# e-programmer.net
KiCad netlist of a schematic drawn in EAGLE
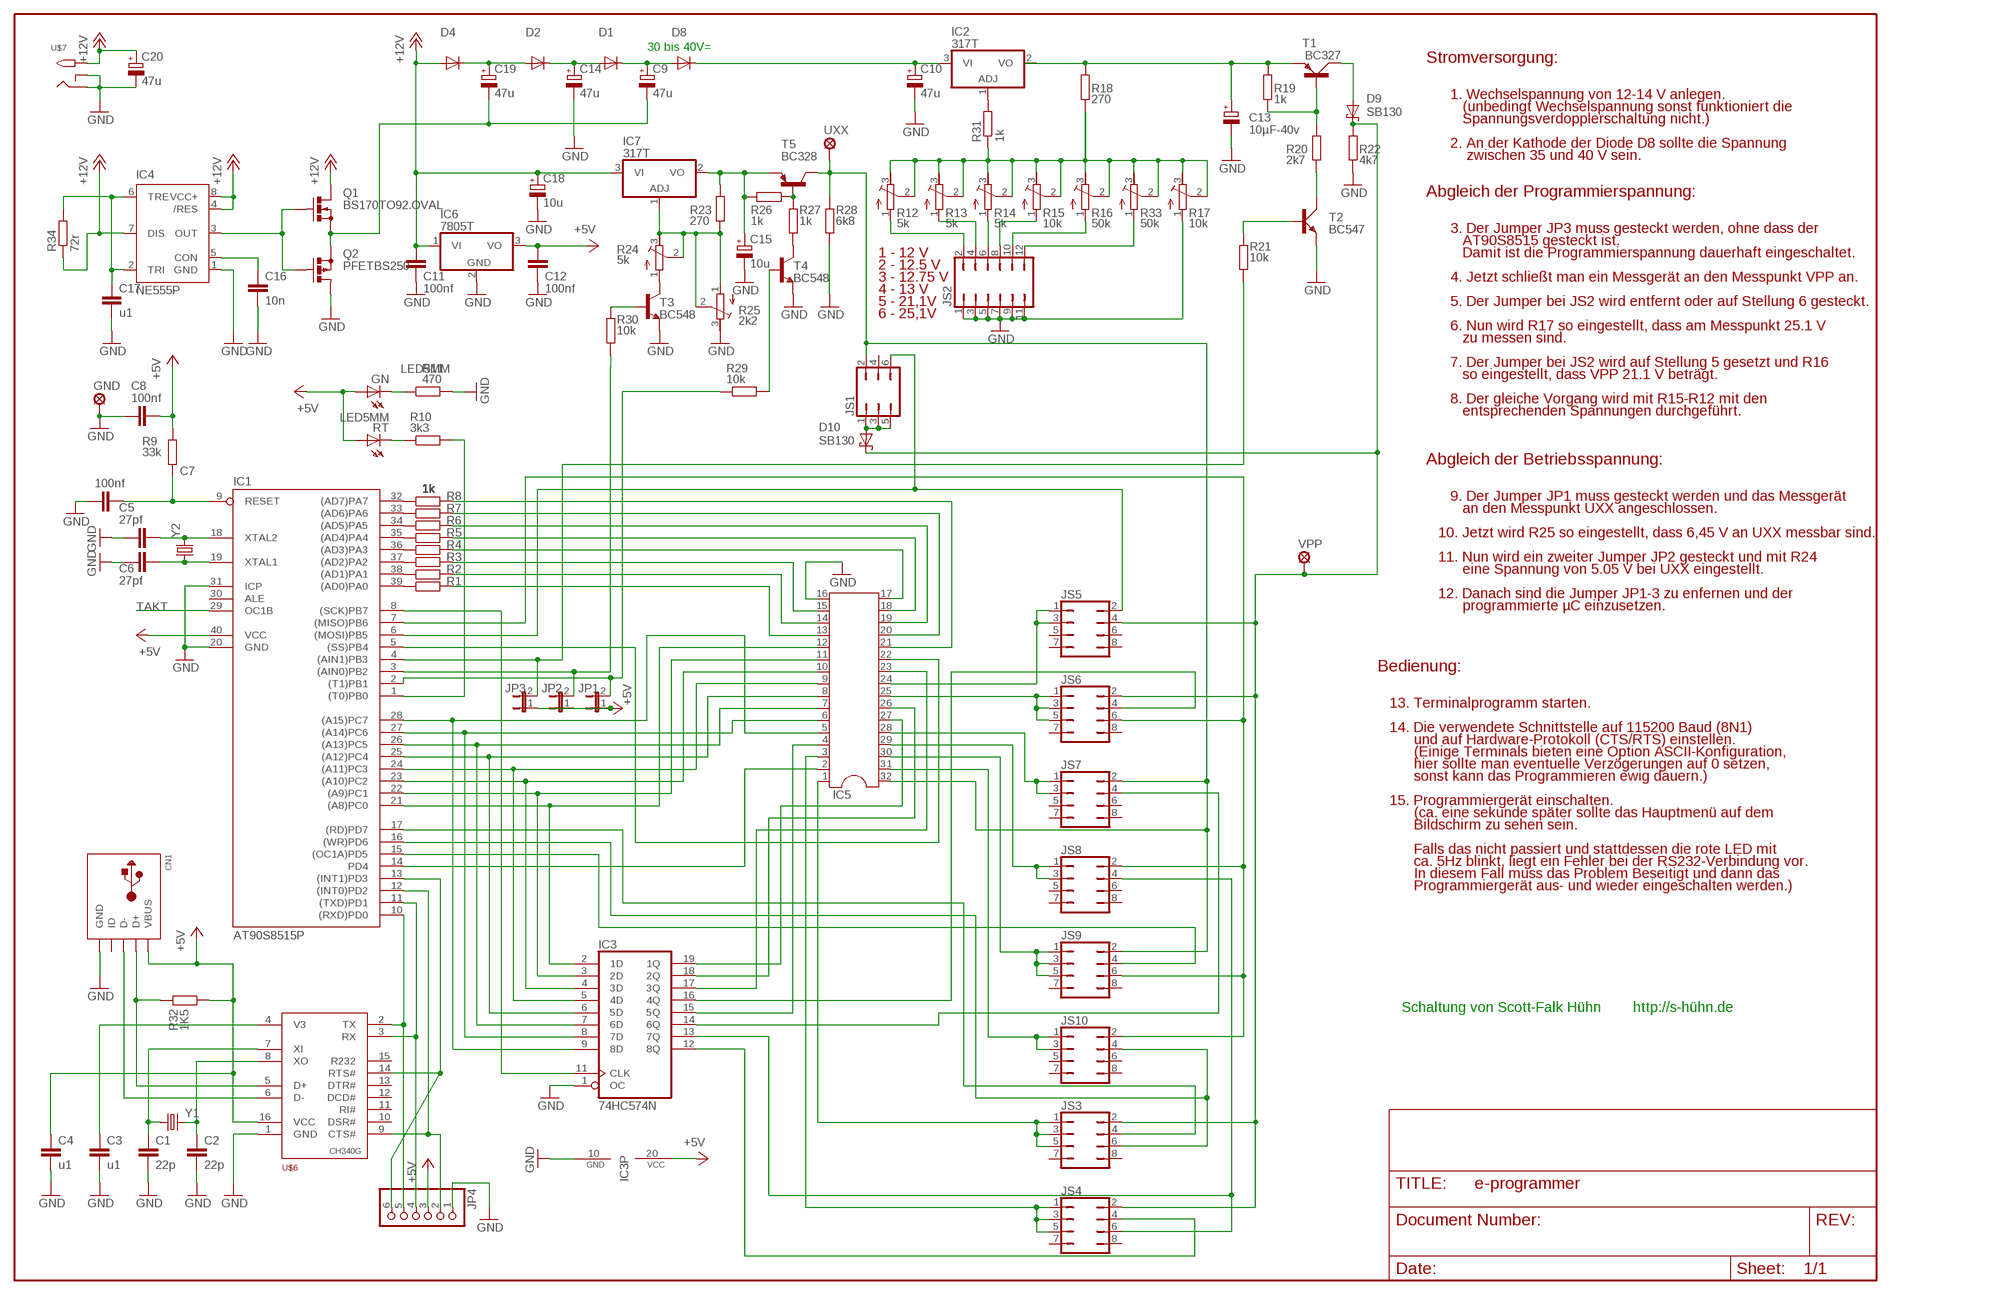
[diagram p0: schematic, sheet 1]

(export (version "E")
  (design (tool "Eeschema 10.0.6"))
  (components
    (comp (ref "C1")
      (value "22p")
      (footprint "eagle-import:C025-025X050")
      (libsource (lib "eagle-import") (part "C-EU025-025X050"))
    )
    (comp (ref "C2")
      (value "22p")
      (footprint "eagle-import:C025-025X050")
      (libsource (lib "eagle-import") (part "C-EU025-025X050"))
    )
    (comp (ref "C3")
      (value "u1")
      (footprint "eagle-import:C025-025X050")
      (libsource (lib "eagle-import") (part "C-EU025-025X050"))
    )
    (comp (ref "C4")
      (value "u1")
      (footprint "eagle-import:C025-025X050")
      (libsource (lib "eagle-import") (part "C-EU025-025X050"))
    )
    (comp (ref "C5")
      (value "27pf")
      (footprint "eagle-import:C025-024X044")
      (libsource (lib "eagle-import") (part "C-EU025-024X044"))
    )
    (comp (ref "C6")
      (value "27pf")
      (footprint "eagle-import:C025-024X044")
      (libsource (lib "eagle-import") (part "C-EU025-024X044"))
    )
    (comp (ref "C7")
      (value "100nf")
      (footprint "eagle-import:C025-024X044")
      (libsource (lib "eagle-import") (part "C-EU025-024X044"))
    )
    (comp (ref "C8")
      (value "100nf")
      (footprint "eagle-import:C025-024X044")
      (libsource (lib "eagle-import") (part "C-EU025-024X044"))
    )
    (comp (ref "C9")
      (value "47u")
      (footprint "eagle-import:E2,5-7")
      (libsource (lib "eagle-import") (part "CPOL-EUE2.5-7"))
    )
    (comp (ref "C10")
      (value "47u")
      (footprint "eagle-import:E2,5-7")
      (libsource (lib "eagle-import") (part "CPOL-EUE2.5-7"))
    )
    (comp (ref "C11")
      (value "100nf")
      (footprint "eagle-import:C025-024X044")
      (libsource (lib "eagle-import") (part "C-EU025-024X044"))
    )
    (comp (ref "C12")
      (value "100nf")
      (footprint "eagle-import:C025-024X044")
      (libsource (lib "eagle-import") (part "C-EU025-024X044"))
    )
    (comp (ref "C13")
      (value "10µF-40v")
      (footprint "eagle-import:E2,5-5")
      (libsource (lib "eagle-import") (part "CPOL-EUE2.5-5"))
    )
    (comp (ref "C14")
      (value "47u")
      (footprint "eagle-import:E2,5-7")
      (libsource (lib "eagle-import") (part "CPOL-EUE2.5-7"))
    )
    (comp (ref "C15")
      (value "10u")
      (footprint "eagle-import:E2,5-7")
      (libsource (lib "eagle-import") (part "CPOL-EUE2.5-7"))
    )
    (comp (ref "C16")
      (value "10n")
      (footprint "eagle-import:C025-025X050")
      (libsource (lib "eagle-import") (part "C-EU025-025X050"))
    )
    (comp (ref "C17")
      (value "u1")
      (footprint "eagle-import:C025-025X050")
      (libsource (lib "eagle-import") (part "C-EU025-025X050"))
    )
    (comp (ref "C18")
      (value "10u")
      (footprint "eagle-import:E2,5-7")
      (libsource (lib "eagle-import") (part "CPOL-EUE2.5-7"))
    )
    (comp (ref "C19")
      (value "47u")
      (footprint "eagle-import:E2,5-7")
      (libsource (lib "eagle-import") (part "CPOL-EUE2.5-7"))
    )
    (comp (ref "C20")
      (value "47u")
      (footprint "eagle-import:E2,5-7")
      (libsource (lib "eagle-import") (part "CPOL-EUE2.5-7"))
    )
    (comp (ref "CN1")
      (value "USBTHM")
      (footprint "eagle-import:USB-MINIB-THM")
      (libsource (lib "eagle-import") (part "USBTHM"))
    )
    (comp (ref "D1")
      (value "1N4004")
      (footprint "eagle-import:DO35-10")
      (libsource (lib "eagle-import") (part "DIODE-DO35-10"))
    )
    (comp (ref "D2")
      (value "1N4004")
      (footprint "eagle-import:DO35-10")
      (libsource (lib "eagle-import") (part "DIODE-DO35-10"))
    )
    (comp (ref "D4")
      (value "1N4004")
      (footprint "eagle-import:DO35-10")
      (libsource (lib "eagle-import") (part "DIODE-DO35-10"))
    )
    (comp (ref "D8")
      (value "1N4004")
      (footprint "eagle-import:DO35-10")
      (libsource (lib "eagle-import") (part "DIODE-DO35-10"))
    )
    (comp (ref "D9")
      (value "SB130")
      (footprint "eagle-import:DO35-7")
      (libsource (lib "eagle-import") (part "SCHOTTKY-DIODEDO35-7"))
    )
    (comp (ref "D10")
      (value "SB130")
      (footprint "eagle-import:DO35-7")
      (libsource (lib "eagle-import") (part "SCHOTTKY-DIODEDO35-7"))
    )
    (comp (ref "GN")
      (value "LED5MM")
      (footprint "eagle-import:LED5MM")
      (libsource (lib "eagle-import") (part "LED5MM"))
    )
    (comp (ref "GND")
      (value "LSP10")
      (footprint "eagle-import:LSP10")
      (libsource (lib "eagle-import") (part "LSP10"))
    )
    (comp (ref "IC1")
      (value "AT90S8515P")
      (footprint "eagle-import:DIL40")
      (libsource (lib "eagle-import") (part "AT90S8515P"))
    )
    (comp (ref "IC2")
      (value "317T")
      (footprint "eagle-import:TO220H")
      (libsource (lib "eagle-import") (part "317T"))
    )
    (comp (ref "IC3")
      (value "74HC574N")
      (footprint "eagle-import:DIL20")
      (libsource (lib "eagle-import") (part "74574NHC"))
    )
    (comp (ref "IC4")
      (value "NE555P")
      (footprint "eagle-import:DIL-08")
      (fields (field (name "MF") "Arrow Electronics") (field (name "MPN") "NE555N"))
      (libsource (lib "eagle-import") (part "NE555P"))
    )
    (comp (ref "IC5")
      (value "DIL32")
      (footprint "eagle-import:DIL32")
      (libsource (lib "eagle-import") (part "DIL32"))
    )
    (comp (ref "IC6")
      (value "7805T")
      (footprint "eagle-import:TO220H")
      (libsource (lib "eagle-import") (part "78T05"))
    )
    (comp (ref "IC7")
      (value "317T")
      (footprint "eagle-import:TO220H")
      (libsource (lib "eagle-import") (part "317T"))
    )
    (comp (ref "JP1")
      (value "JP1E")
      (footprint "eagle-import:JP1")
      (libsource (lib "eagle-import") (part "JP1E"))
    )
    (comp (ref "JP2")
      (value "JP1E")
      (footprint "eagle-import:JP1")
      (libsource (lib "eagle-import") (part "JP1E"))
    )
    (comp (ref "JP3")
      (value "JP1E")
      (footprint "eagle-import:JP1")
      (libsource (lib "eagle-import") (part "JP1E"))
    )
    (comp (ref "JP4")
      (value "PINHD-1X6")
      (footprint "eagle-import:1X06")
      (libsource (lib "eagle-import") (part "PINHD-1X6"))
    )
    (comp (ref "JS1")
      (value "JP3Q")
      (footprint "eagle-import:JP3Q")
      (libsource (lib "eagle-import") (part "JP3Q"))
    )
    (comp (ref "JS2")
      (value "JP6Q")
      (footprint "eagle-import:JP6Q")
      (libsource (lib "eagle-import") (part "JP6Q"))
    )
    (comp (ref "JS3")
      (value "JP4Q")
      (footprint "eagle-import:JP4Q")
      (libsource (lib "eagle-import") (part "JP4Q"))
    )
    (comp (ref "JS4")
      (value "JP4Q")
      (footprint "eagle-import:JP4Q")
      (libsource (lib "eagle-import") (part "JP4Q"))
    )
    (comp (ref "JS5")
      (value "JP4Q")
      (footprint "eagle-import:JP4Q")
      (libsource (lib "eagle-import") (part "JP4Q"))
    )
    (comp (ref "JS6")
      (value "JP4Q")
      (footprint "eagle-import:JP4Q")
      (libsource (lib "eagle-import") (part "JP4Q"))
    )
    (comp (ref "JS7")
      (value "JP4Q")
      (footprint "eagle-import:JP4Q")
      (libsource (lib "eagle-import") (part "JP4Q"))
    )
    (comp (ref "JS8")
      (value "JP4Q")
      (footprint "eagle-import:JP4Q")
      (libsource (lib "eagle-import") (part "JP4Q"))
    )
    (comp (ref "JS9")
      (value "JP4Q")
      (footprint "eagle-import:JP4Q")
      (libsource (lib "eagle-import") (part "JP4Q"))
    )
    (comp (ref "JS10")
      (value "JP4Q")
      (footprint "eagle-import:JP4Q")
      (libsource (lib "eagle-import") (part "JP4Q"))
    )
    (comp (ref "Q1")
      (value "BS170TO92.OVAL")
      (footprint "eagle-import:TO92-OVAL")
      (libsource (lib "eagle-import") (part "BS170TO92.OVAL"))
    )
    (comp (ref "Q2")
      (value "PFETBS250")
      (footprint "eagle-import:TO92-OVAL")
      (libsource (lib "eagle-import") (part "PFETBS250"))
    )
    (comp (ref "R1")
      (value "1k")
      (footprint "eagle-import:0207_7")
      (libsource (lib "eagle-import") (part "R-EU_0207/7"))
    )
    (comp (ref "R2")
      (value "1k")
      (footprint "eagle-import:0207_7")
      (libsource (lib "eagle-import") (part "R-EU_0207/7"))
    )
    (comp (ref "R3")
      (value "1k")
      (footprint "eagle-import:0207_7")
      (libsource (lib "eagle-import") (part "R-EU_0207/7"))
    )
    (comp (ref "R4")
      (value "1k")
      (footprint "eagle-import:0207_7")
      (libsource (lib "eagle-import") (part "R-EU_0207/7"))
    )
    (comp (ref "R5")
      (value "1k")
      (footprint "eagle-import:0207_7")
      (libsource (lib "eagle-import") (part "R-EU_0207/7"))
    )
    (comp (ref "R6")
      (value "1k")
      (footprint "eagle-import:0207_7")
      (libsource (lib "eagle-import") (part "R-EU_0207/7"))
    )
    (comp (ref "R7")
      (value "1k")
      (footprint "eagle-import:0207_7")
      (libsource (lib "eagle-import") (part "R-EU_0207/7"))
    )
    (comp (ref "R8")
      (value "1k")
      (footprint "eagle-import:0207_7")
      (libsource (lib "eagle-import") (part "R-EU_0207/7"))
    )
    (comp (ref "R9")
      (value "33k")
      (footprint "eagle-import:0204_7")
      (libsource (lib "eagle-import") (part "R-EU_0204/7"))
    )
    (comp (ref "R10")
      (value "3k3")
      (footprint "eagle-import:0204_7")
      (libsource (lib "eagle-import") (part "R-EU_0204/7"))
    )
    (comp (ref "R11")
      (value "470")
      (footprint "eagle-import:0204_7")
      (libsource (lib "eagle-import") (part "R-EU_0204/7"))
    )
    (comp (ref "R12")
      (value "5k")
      (footprint "eagle-import:RTRIM3296W")
      (libsource (lib "eagle-import") (part "R-TRIMM3296W"))
    )
    (comp (ref "R13")
      (value "5k")
      (footprint "eagle-import:RTRIM3296W")
      (libsource (lib "eagle-import") (part "R-TRIMM3296W"))
    )
    (comp (ref "R14")
      (value "5k")
      (footprint "eagle-import:RTRIM3296W")
      (libsource (lib "eagle-import") (part "R-TRIMM3296W"))
    )
    (comp (ref "R15")
      (value "10k")
      (footprint "eagle-import:RTRIM3296W")
      (libsource (lib "eagle-import") (part "R-TRIMM3296W"))
    )
    (comp (ref "R16")
      (value "50k")
      (footprint "eagle-import:RTRIM3296W")
      (libsource (lib "eagle-import") (part "R-TRIMM3296W"))
    )
    (comp (ref "R17")
      (value "10k")
      (footprint "eagle-import:RTRIM3296W")
      (libsource (lib "eagle-import") (part "R-TRIMM3296W"))
    )
    (comp (ref "R18")
      (value "270")
      (footprint "eagle-import:0207_7")
      (libsource (lib "eagle-import") (part "R-EU_0207/7"))
    )
    (comp (ref "R19")
      (value "1k")
      (footprint "eagle-import:0207_7")
      (libsource (lib "eagle-import") (part "R-EU_0207/7"))
    )
    (comp (ref "R20")
      (value "2k7")
      (footprint "eagle-import:0207_7")
      (libsource (lib "eagle-import") (part "R-EU_0207/7"))
    )
    (comp (ref "R21")
      (value "10k")
      (footprint "eagle-import:0207_7")
      (libsource (lib "eagle-import") (part "R-EU_0207/7"))
    )
    (comp (ref "R22")
      (value "4k7")
      (footprint "eagle-import:0207_7")
      (libsource (lib "eagle-import") (part "R-EU_0207/7"))
    )
    (comp (ref "R23")
      (value "270")
      (footprint "eagle-import:0207_7")
      (libsource (lib "eagle-import") (part "R-EU_0207/7"))
    )
    (comp (ref "R24")
      (value "5k")
      (footprint "eagle-import:RTRIM3296W")
      (libsource (lib "eagle-import") (part "R-TRIMM3296W"))
    )
    (comp (ref "R25")
      (value "2k2")
      (footprint "eagle-import:RTRIM3296W")
      (libsource (lib "eagle-import") (part "R-TRIMM3296W"))
    )
    (comp (ref "R26")
      (value "1k")
      (footprint "eagle-import:0207_7")
      (libsource (lib "eagle-import") (part "R-EU_0207/7"))
    )
    (comp (ref "R27")
      (value "1k")
      (footprint "eagle-import:0207_7")
      (libsource (lib "eagle-import") (part "R-EU_0207/7"))
    )
    (comp (ref "R28")
      (value "6k8")
      (footprint "eagle-import:0207_7")
      (libsource (lib "eagle-import") (part "R-EU_0207/7"))
    )
    (comp (ref "R29")
      (value "10k")
      (footprint "eagle-import:0207_7")
      (libsource (lib "eagle-import") (part "R-EU_0207/7"))
    )
    (comp (ref "R30")
      (value "10k")
      (footprint "eagle-import:0207_7")
      (libsource (lib "eagle-import") (part "R-EU_0207/7"))
    )
    (comp (ref "R31")
      (value "1k")
      (footprint "eagle-import:0207_7")
      (libsource (lib "eagle-import") (part "R-EU_0207/7"))
    )
    (comp (ref "R32")
      (value "1K5")
      (footprint "eagle-import:0204_7")
      (libsource (lib "eagle-import") (part "R-EU_0204/7"))
    )
    (comp (ref "R33")
      (value "50k")
      (footprint "eagle-import:RTRIM3296W")
      (libsource (lib "eagle-import") (part "R-TRIMM3296W"))
    )
    (comp (ref "R34")
      (value "72r")
      (footprint "eagle-import:0204_7")
      (libsource (lib "eagle-import") (part "R-EU_0204/7"))
    )
    (comp (ref "RT")
      (value "LED5MM")
      (footprint "eagle-import:LED5MM")
      (libsource (lib "eagle-import") (part "LED5MM"))
    )
    (comp (ref "T1")
      (value "BC327")
      (footprint "eagle-import:SOT54A")
      (libsource (lib "eagle-import") (part "transistor-small-signal_BC327"))
    )
    (comp (ref "T2")
      (value "BC547")
      (footprint "eagle-import:SOT54A")
      (libsource (lib "eagle-import") (part "transistor-small-signal_BC547"))
    )
    (comp (ref "T3")
      (value "BC548")
      (footprint "eagle-import:TO92")
      (libsource (lib "eagle-import") (part "BC547"))
    )
    (comp (ref "T4")
      (value "BC548")
      (footprint "eagle-import:TO92")
      (libsource (lib "eagle-import") (part "BC547"))
    )
    (comp (ref "T5")
      (value "BC328")
      (footprint "eagle-import:TO92")
      (libsource (lib "eagle-import") (part "BC327"))
    )
    (comp (ref "U$6")
      (value "CH340G")
      (footprint "eagle-import:SO16")
      (libsource (lib "eagle-import") (part "CH340G"))
    )
    (comp (ref "U$7")
      (value "2.1MMJACKTHM")
      (footprint "eagle-import:PJ-102A")
      (libsource (lib "eagle-import") (part "2.1MMJACKTHM"))
    )
    (comp (ref "UXX")
      (value "LSP10")
      (footprint "eagle-import:LSP10")
      (libsource (lib "eagle-import") (part "LSP10"))
    )
    (comp (ref "VPP")
      (value "LSP10")
      (footprint "eagle-import:LSP10")
      (libsource (lib "eagle-import") (part "LSP10"))
    )
    (comp (ref "Y1")
      (value "CRYSTALHC49US")
      (footprint "eagle-import:HC49US")
      (libsource (lib "eagle-import") (part "CRYSTALHC49US"))
    )
    (comp (ref "Y2")
      (value "CRYSTALHC49US")
      (footprint "eagle-import:HC49US")
      (libsource (lib "eagle-import") (part "CRYSTALHC49US"))
    )
  )
  (nets
    (net (code "1") (name "+5V") (class "Default")
      (node (ref "C12") (pin "1") (pinfunction "1_1") (pintype "passive"))
      (node (ref "C4") (pin "1") (pinfunction "1_1") (pintype "passive"))
      (node (ref "C8") (pin "2") (pinfunction "2_2") (pintype "passive"))
      (node (ref "CN1") (pin "VBUS") (pinfunction "VBUS_VBUS") (pintype "power_in"))
      (node (ref "GN") (pin "A") (pinfunction "A_A") (pintype "passive"))
      (node (ref "IC1") (pin "40") (pinfunction "VCC_40") (pintype "power_in"))
      (node (ref "IC3") (pin "20") (pinfunction "VCC_20") (pintype "power_in"))
      (node (ref "IC6") (pin "3") (pinfunction "VO_3") (pintype "passive"))
      (node (ref "JP1") (pin "1") (pinfunction "1_1") (pintype "passive"))
      (node (ref "JP2") (pin "1") (pinfunction "1_1") (pintype "passive"))
      (node (ref "JP3") (pin "1") (pinfunction "1_1") (pintype "passive"))
      (node (ref "JP4") (pin "3") (pinfunction "3_3") (pintype "passive"))
      (node (ref "R32") (pin "1") (pinfunction "1_1") (pintype "passive"))
      (node (ref "R9") (pin "2") (pinfunction "2_2") (pintype "passive"))
      (node (ref "RT") (pin "A") (pinfunction "A_A") (pintype "passive"))
      (node (ref "U$6") (pin "16") (pinfunction "VCC_16") (pintype "bidirectional"))
    )
    (net (code "2") (name "+12V") (class "Default")
      (node (ref "C11") (pin "1") (pinfunction "1_1") (pintype "passive"))
      (node (ref "C18") (pin "+") (pinfunction "+_+") (pintype "passive"))
      (node (ref "C20") (pin "+") (pinfunction "+_+") (pintype "passive"))
      (node (ref "D4") (pin "A") (pinfunction "A_A") (pintype "passive"))
      (node (ref "IC4") (pin "4") (pinfunction "/RES_4") (pintype "input"))
      (node (ref "IC4") (pin "7") (pinfunction "DIS_7") (pintype "input"))
      (node (ref "IC4") (pin "8") (pinfunction "VCC+_8") (pintype "power_in"))
      (node (ref "IC6") (pin "1") (pinfunction "VI_1") (pintype "input"))
      (node (ref "IC7") (pin "3") (pinfunction "VI_3") (pintype "input"))
      (node (ref "Q1") (pin "1") (pinfunction "D_1") (pintype "passive"))
      (node (ref "R34") (pin "1") (pinfunction "1_1") (pintype "passive"))
      (node (ref "U$7") (pin "TIP") (pinfunction "TIP_TIP") (pintype "bidirectional"))
    )
    (net (code "3") (name "/TAKT") (class "Default")
      (node (ref "IC1") (pin "29") (pinfunction "OC1B_29") (pintype "bidirectional"))
    )
    (net (code "4") (name "/VCC_5{slash}6") (class "Default")
      (node (ref "IC1") (pin "3") (pinfunction "(AIN0)PB2_3") (pintype "bidirectional"))
      (node (ref "JP2") (pin "2") (pinfunction "2_2") (pintype "passive"))
      (node (ref "R30") (pin "1") (pinfunction "1_1") (pintype "passive"))
    )
    (net (code "5") (name "GND") (class "Default")
      (node (ref "C1") (pin "2") (pinfunction "2_2") (pintype "passive"))
      (node (ref "C10") (pin "-") (pinfunction "-_-") (pintype "passive"))
      (node (ref "C11") (pin "2") (pinfunction "2_2") (pintype "passive"))
      (node (ref "C12") (pin "2") (pinfunction "2_2") (pintype "passive"))
      (node (ref "C13") (pin "-") (pinfunction "-_-") (pintype "passive"))
      (node (ref "C14") (pin "-") (pinfunction "-_-") (pintype "passive"))
      (node (ref "C15") (pin "-") (pinfunction "-_-") (pintype "passive"))
      (node (ref "C16") (pin "2") (pinfunction "2_2") (pintype "passive"))
      (node (ref "C17") (pin "2") (pinfunction "2_2") (pintype "passive"))
      (node (ref "C18") (pin "-") (pinfunction "-_-") (pintype "passive"))
      (node (ref "C2") (pin "2") (pinfunction "2_2") (pintype "passive"))
      (node (ref "C20") (pin "-") (pinfunction "-_-") (pintype "passive"))
      (node (ref "C3") (pin "2") (pinfunction "2_2") (pintype "passive"))
      (node (ref "C4") (pin "2") (pinfunction "2_2") (pintype "passive"))
      (node (ref "C5") (pin "1") (pinfunction "1_1") (pintype "passive"))
      (node (ref "C6") (pin "1") (pinfunction "1_1") (pintype "passive"))
      (node (ref "C7") (pin "1") (pinfunction "1_1") (pintype "passive"))
      (node (ref "C8") (pin "1") (pinfunction "1_1") (pintype "passive"))
      (node (ref "CN1") (pin "GND") (pinfunction "GND_GND") (pintype "power_in"))
      (node (ref "GND") (pin "MP") (pinfunction "MP_MP") (pintype "passive"))
      (node (ref "IC1") (pin "20") (pinfunction "GND_20") (pintype "power_in"))
      (node (ref "IC1") (pin "31") (pinfunction "ICP_31") (pintype "bidirectional"))
      (node (ref "IC3") (pin "1") (pinfunction "OC_1") (pintype "input"))
      (node (ref "IC3") (pin "10") (pinfunction "GND_10") (pintype "power_in"))
      (node (ref "IC4") (pin "1") (pinfunction "GND_1") (pintype "power_in"))
      (node (ref "IC5") (pin "16") (pinfunction "16_16") (pintype "passive"))
      (node (ref "IC6") (pin "2") (pinfunction "GND_2") (pintype "passive"))
      (node (ref "JP4") (pin "1") (pinfunction "1_1") (pintype "passive"))
      (node (ref "JS2") (pin "1") (pinfunction "1_1") (pintype "passive"))
      (node (ref "JS2") (pin "11") (pinfunction "11_11") (pintype "passive"))
      (node (ref "JS2") (pin "3") (pinfunction "3_3") (pintype "passive"))
      (node (ref "JS2") (pin "5") (pinfunction "5_5") (pintype "passive"))
      (node (ref "JS2") (pin "7") (pinfunction "7_7") (pintype "passive"))
      (node (ref "JS2") (pin "9") (pinfunction "9_9") (pintype "passive"))
      (node (ref "Q2") (pin "1") (pinfunction "D_1") (pintype "passive"))
      (node (ref "R11") (pin "2") (pinfunction "2_2") (pintype "passive"))
      (node (ref "R17") (pin "1") (pinfunction "E_1") (pintype "passive"))
      (node (ref "R22") (pin "1") (pinfunction "1_1") (pintype "passive"))
      (node (ref "R25") (pin "3") (pinfunction "A_3") (pintype "passive"))
      (node (ref "R28") (pin "1") (pinfunction "1_1") (pintype "passive"))
      (node (ref "T2") (pin "E") (pinfunction "E_E") (pintype "passive"))
      (node (ref "T3") (pin "1") (pinfunction "E_1") (pintype "passive"))
      (node (ref "T4") (pin "1") (pinfunction "E_1") (pintype "passive"))
      (node (ref "U$6") (pin "1") (pinfunction "GND_1") (pintype "bidirectional"))
      (node (ref "U$7") (pin "RING") (pinfunction "RING_RING") (pintype "bidirectional"))
      (node (ref "U$7") (pin "RING_SW") (pinfunction "RING_SW_RING_SW") (pintype "bidirectional"))
    )
    (net (code "6") (name "Net-(C9-Pad+)") (class "Default")
      (node (ref "C9") (pin "+") (pinfunction "+_+") (pintype "passive"))
      (node (ref "D1") (pin "C") (pinfunction "C_C") (pintype "passive"))
      (node (ref "D8") (pin "A") (pinfunction "A_A") (pintype "passive"))
    )
    (net (code "7") (name "Net-(C14-Pad+)") (class "Default")
      (node (ref "C14") (pin "+") (pinfunction "+_+") (pintype "passive"))
      (node (ref "D1") (pin "A") (pinfunction "A_A") (pintype "passive"))
      (node (ref "D2") (pin "C") (pinfunction "C_C") (pintype "passive"))
    )
    (net (code "8") (name "Net-(C19-Pad+)") (class "Default")
      (node (ref "C19") (pin "+") (pinfunction "+_+") (pintype "passive"))
      (node (ref "D2") (pin "A") (pinfunction "A_A") (pintype "passive"))
      (node (ref "D4") (pin "C") (pinfunction "C_C") (pintype "passive"))
    )
    (net (code "9") (name "Net-(D9-PadA)") (class "Default")
      (node (ref "D9") (pin "A") (pinfunction "A_A") (pintype "passive"))
      (node (ref "T1") (pin "C") (pinfunction "C_C") (pintype "passive"))
    )
    (net (code "10") (name "Net-(D10-PadA)") (class "Default")
      (node (ref "D10") (pin "A") (pinfunction "A_A") (pintype "passive"))
      (node (ref "JS1") (pin "1") (pinfunction "1_1") (pintype "passive"))
      (node (ref "JS1") (pin "3") (pinfunction "3_3") (pintype "passive"))
      (node (ref "JS1") (pin "5") (pinfunction "5_5") (pintype "passive"))
    )
    (net (code "11") (name "Net-(D10-PadC)") (class "Default")
      (node (ref "D10") (pin "C") (pinfunction "C_C") (pintype "passive"))
      (node (ref "D9") (pin "C") (pinfunction "C_C") (pintype "passive"))
      (node (ref "JS3") (pin "2") (pinfunction "2_2") (pintype "passive"))
      (node (ref "JS4") (pin "2") (pinfunction "2_2") (pintype "passive"))
      (node (ref "JS5") (pin "4") (pinfunction "4_4") (pintype "passive"))
      (node (ref "JS6") (pin "2") (pinfunction "2_2") (pintype "passive"))
      (node (ref "R22") (pin "2") (pinfunction "2_2") (pintype "passive"))
      (node (ref "VPP") (pin "MP") (pinfunction "MP_MP") (pintype "passive"))
    )
    (net (code "12") (name "Net-(GN-C)") (class "Default")
      (node (ref "GN") (pin "K") (pinfunction "C_K") (pintype "passive"))
      (node (ref "R11") (pin "1") (pinfunction "1_1") (pintype "passive"))
    )
    (net (code "13") (name "Net-(IC1-(A8)PC0)") (class "Default")
      (node (ref "IC1") (pin "21") (pinfunction "(A8)PC0_21") (pintype "bidirectional"))
      (node (ref "IC3") (pin "2") (pinfunction "1D_2") (pintype "input"))
      (node (ref "IC5") (pin "12") (pinfunction "12_12") (pintype "passive"))
    )
    (net (code "14") (name "Net-(IC1-(A9)PC1)") (class "Default")
      (node (ref "IC1") (pin "22") (pinfunction "(A9)PC1_22") (pintype "bidirectional"))
      (node (ref "IC3") (pin "3") (pinfunction "2D_3") (pintype "input"))
      (node (ref "IC5") (pin "11") (pinfunction "11_11") (pintype "passive"))
    )
    (net (code "15") (name "Net-(IC1-(A10)PC2)") (class "Default")
      (node (ref "IC1") (pin "23") (pinfunction "(A10)PC2_23") (pintype "bidirectional"))
      (node (ref "IC3") (pin "4") (pinfunction "3D_4") (pintype "input"))
      (node (ref "IC5") (pin "10") (pinfunction "10_10") (pintype "passive"))
    )
    (net (code "16") (name "Net-(IC1-(A11)PC3)") (class "Default")
      (node (ref "IC1") (pin "24") (pinfunction "(A11)PC3_24") (pintype "bidirectional"))
      (node (ref "IC3") (pin "5") (pinfunction "4D_5") (pintype "input"))
      (node (ref "IC5") (pin "9") (pinfunction "9_9") (pintype "passive"))
    )
    (net (code "17") (name "Net-(IC1-(A12)PC4)") (class "Default")
      (node (ref "IC1") (pin "25") (pinfunction "(A12)PC4_25") (pintype "bidirectional"))
      (node (ref "IC3") (pin "6") (pinfunction "5D_6") (pintype "input"))
      (node (ref "IC5") (pin "8") (pinfunction "8_8") (pintype "passive"))
    )
    (net (code "18") (name "Net-(IC1-(A13)PC5)") (class "Default")
      (node (ref "IC1") (pin "26") (pinfunction "(A13)PC5_26") (pintype "bidirectional"))
      (node (ref "IC3") (pin "7") (pinfunction "6D_7") (pintype "input"))
      (node (ref "IC5") (pin "7") (pinfunction "7_7") (pintype "passive"))
    )
    (net (code "19") (name "Net-(IC1-(A14)PC6)") (class "Default")
      (node (ref "IC1") (pin "27") (pinfunction "(A14)PC6_27") (pintype "bidirectional"))
      (node (ref "IC3") (pin "8") (pinfunction "7D_8") (pintype "input"))
      (node (ref "IC5") (pin "6") (pinfunction "6_6") (pintype "passive"))
    )
    (net (code "20") (name "Net-(IC1-(A15)PC7)") (class "Default")
      (node (ref "IC1") (pin "28") (pinfunction "(A15)PC7_28") (pintype "bidirectional"))
      (node (ref "IC3") (pin "9") (pinfunction "8D_9") (pintype "input"))
      (node (ref "IC5") (pin "5") (pinfunction "5_5") (pintype "passive"))
    )
    (net (code "21") (name "Net-(IC1-(AD0)PA0)") (class "Default")
      (node (ref "IC1") (pin "39") (pinfunction "(AD0)PA0_39") (pintype "bidirectional"))
      (node (ref "R1") (pin "1") (pinfunction "1_1") (pintype "passive"))
    )
    (net (code "22") (name "Net-(IC1-(AD1)PA1)") (class "Default")
      (node (ref "IC1") (pin "38") (pinfunction "(AD1)PA1_38") (pintype "bidirectional"))
      (node (ref "R2") (pin "1") (pinfunction "1_1") (pintype "passive"))
    )
    (net (code "23") (name "Net-(IC1-(AD2)PA2)") (class "Default")
      (node (ref "IC1") (pin "37") (pinfunction "(AD2)PA2_37") (pintype "bidirectional"))
      (node (ref "R3") (pin "1") (pinfunction "1_1") (pintype "passive"))
    )
    (net (code "24") (name "Net-(IC1-(AD3)PA3)") (class "Default")
      (node (ref "IC1") (pin "36") (pinfunction "(AD3)PA3_36") (pintype "bidirectional"))
      (node (ref "R4") (pin "1") (pinfunction "1_1") (pintype "passive"))
    )
    (net (code "25") (name "Net-(IC1-(AD4)PA4)") (class "Default")
      (node (ref "IC1") (pin "35") (pinfunction "(AD4)PA4_35") (pintype "bidirectional"))
      (node (ref "R5") (pin "1") (pinfunction "1_1") (pintype "passive"))
    )
    (net (code "26") (name "Net-(IC1-(AD5)PA5)") (class "Default")
      (node (ref "IC1") (pin "34") (pinfunction "(AD5)PA5_34") (pintype "bidirectional"))
      (node (ref "R6") (pin "1") (pinfunction "1_1") (pintype "passive"))
    )
    (net (code "27") (name "Net-(IC1-(AD6)PA6)") (class "Default")
      (node (ref "IC1") (pin "33") (pinfunction "(AD6)PA6_33") (pintype "bidirectional"))
      (node (ref "R7") (pin "1") (pinfunction "1_1") (pintype "passive"))
    )
    (net (code "28") (name "Net-(IC1-(AD7)PA7)") (class "Default")
      (node (ref "IC1") (pin "32") (pinfunction "(AD7)PA7_32") (pintype "bidirectional"))
      (node (ref "R8") (pin "1") (pinfunction "1_1") (pintype "passive"))
    )
    (net (code "29") (name "Net-(IC1-(AIN1)PB3)") (class "Default")
      (node (ref "IC1") (pin "4") (pinfunction "(AIN1)PB3_4") (pintype "bidirectional"))
      (node (ref "JP3") (pin "2") (pinfunction "2_2") (pintype "passive"))
      (node (ref "R21") (pin "1") (pinfunction "1_1") (pintype "passive"))
    )
    (net (code "30") (name "Net-(IC1-(INT0)PD2)") (class "Default")
      (node (ref "IC1") (pin "12") (pinfunction "(INT0)PD2_12") (pintype "bidirectional"))
      (node (ref "JP4") (pin "2") (pinfunction "2_2") (pintype "passive"))
      (node (ref "U$6") (pin "9") (pinfunction "CTS#_9") (pintype "bidirectional"))
    )
    (net (code "31") (name "Net-(IC1-(INT1)PD3)") (class "Default")
      (node (ref "IC1") (pin "13") (pinfunction "(INT1)PD3_13") (pintype "bidirectional"))
      (node (ref "JP4") (pin "6") (pinfunction "6_6") (pintype "passive"))
      (node (ref "U$6") (pin "14") (pinfunction "RTS#_14") (pintype "bidirectional"))
    )
    (net (code "32") (name "Net-(IC1-(MISO)PB6)") (class "Default")
      (node (ref "IC1") (pin "7") (pinfunction "(MISO)PB6_7") (pintype "bidirectional"))
      (node (ref "JS10") (pin "2") (pinfunction "2_2") (pintype "passive"))
      (node (ref "JS6") (pin "6") (pinfunction "6_6") (pintype "passive"))
      (node (ref "JS8") (pin "2") (pinfunction "2_2") (pintype "passive"))
      (node (ref "JS9") (pin "6") (pinfunction "6_6") (pintype "passive"))
    )
    (net (code "33") (name "Net-(IC1-(MOSI)PB5)") (class "Default")
      (node (ref "IC1") (pin "6") (pinfunction "(MOSI)PB5_6") (pintype "bidirectional"))
      (node (ref "JS1") (pin "6") (pinfunction "6_6") (pintype "passive"))
      (node (ref "JS5") (pin "2") (pinfunction "2_2") (pintype "passive"))
    )
    (net (code "34") (name "Net-(IC1-(OC1A)PD5)") (class "Default")
      (node (ref "IC1") (pin "15") (pinfunction "(OC1A)PD5_15") (pintype "bidirectional"))
      (node (ref "JS9") (pin "4") (pinfunction "4_4") (pintype "passive"))
    )
    (net (code "35") (name "Net-(IC1-(RD)PD7)") (class "Default")
      (node (ref "IC1") (pin "17") (pinfunction "(RD)PD7_17") (pintype "bidirectional"))
      (node (ref "JS3") (pin "4") (pinfunction "4_4") (pintype "passive"))
    )
    (net (code "36") (name "Net-(IC1-(RXD)PD0)") (class "Default")
      (node (ref "IC1") (pin "10") (pinfunction "(RXD)PD0_10") (pintype "bidirectional"))
      (node (ref "JP4") (pin "5") (pinfunction "5_5") (pintype "passive"))
      (node (ref "U$6") (pin "2") (pinfunction "TX_2") (pintype "bidirectional"))
    )
    (net (code "37") (name "Net-(IC1-(SCK)PB7)") (class "Default")
      (node (ref "IC1") (pin "8") (pinfunction "(SCK)PB7_8") (pintype "bidirectional"))
      (node (ref "IC3") (pin "11") (pinfunction "CLK_11") (pintype "input"))
    )
    (net (code "38") (name "Net-(IC1-(SS)PB4)") (class "Default")
      (node (ref "IC1") (pin "5") (pinfunction "(SS)PB4_5") (pintype "bidirectional"))
      (node (ref "IC5") (pin "22") (pinfunction "22_22") (pintype "passive"))
    )
    (net (code "39") (name "Net-(IC1-(T0)PB0)") (class "Default")
      (node (ref "IC1") (pin "1") (pinfunction "(T0)PB0_1") (pintype "bidirectional"))
      (node (ref "R10") (pin "2") (pinfunction "2_2") (pintype "passive"))
    )
    (net (code "40") (name "Net-(IC1-(T1)PB1)") (class "Default")
      (node (ref "IC1") (pin "2") (pinfunction "(T1)PB1_2") (pintype "bidirectional"))
      (node (ref "JP1") (pin "2") (pinfunction "2_2") (pintype "passive"))
      (node (ref "R29") (pin "1") (pinfunction "1_1") (pintype "passive"))
    )
    (net (code "41") (name "Net-(IC1-(TXD)PD1)") (class "Default")
      (node (ref "IC1") (pin "11") (pinfunction "(TXD)PD1_11") (pintype "bidirectional"))
      (node (ref "JP4") (pin "4") (pinfunction "4_4") (pintype "passive"))
      (node (ref "U$6") (pin "3") (pinfunction "RX_3") (pintype "bidirectional"))
    )
    (net (code "42") (name "Net-(IC1-(WR)PD6)") (class "Default")
      (node (ref "IC1") (pin "16") (pinfunction "(WR)PD6_16") (pintype "bidirectional"))
      (node (ref "JS10") (pin "4") (pinfunction "4_4") (pintype "passive"))
      (node (ref "JS3") (pin "6") (pinfunction "6_6") (pintype "passive"))
    )
    (net (code "43") (name "Net-(IC1-PD4)") (class "Default")
      (node (ref "IC1") (pin "14") (pinfunction "PD4_14") (pintype "bidirectional"))
      (node (ref "IC5") (pin "2") (pinfunction "2_2") (pintype "passive"))
    )
    (net (code "44") (name "Net-(IC1-RESET)") (class "Default")
      (node (ref "C7") (pin "2") (pinfunction "2_2") (pintype "passive"))
      (node (ref "IC1") (pin "9") (pinfunction "RESET_9") (pintype "input"))
      (node (ref "R9") (pin "1") (pinfunction "1_1") (pintype "passive"))
    )
    (net (code "45") (name "Net-(IC1-XTAL1)") (class "Default")
      (node (ref "C6") (pin "2") (pinfunction "2_2") (pintype "passive"))
      (node (ref "IC1") (pin "19") (pinfunction "XTAL1_19") (pintype "bidirectional"))
      (node (ref "Y2") (pin "1") (pinfunction "1_1") (pintype "passive"))
    )
    (net (code "46") (name "Net-(IC1-XTAL2)") (class "Default")
      (node (ref "C5") (pin "2") (pinfunction "2_2") (pintype "passive"))
      (node (ref "IC1") (pin "18") (pinfunction "XTAL2_18") (pintype "bidirectional"))
      (node (ref "Y2") (pin "2") (pinfunction "2_2") (pintype "passive"))
    )
    (net (code "47") (name "Net-(IC2-ADJ)") (class "Default")
      (node (ref "IC2") (pin "1") (pinfunction "ADJ_1") (pintype "input"))
      (node (ref "R31") (pin "2") (pinfunction "2_2") (pintype "passive"))
    )
    (net (code "48") (name "Net-(IC2-VI)") (class "Default")
      (node (ref "C10") (pin "+") (pinfunction "+_+") (pintype "passive"))
      (node (ref "D8") (pin "C") (pinfunction "C_C") (pintype "passive"))
      (node (ref "IC2") (pin "3") (pinfunction "VI_3") (pintype "input"))
    )
    (net (code "49") (name "Net-(IC2-VO)") (class "Default")
      (node (ref "C13") (pin "+") (pinfunction "+_+") (pintype "passive"))
      (node (ref "IC2") (pin "2") (pinfunction "VO_2") (pintype "passive"))
      (node (ref "R18") (pin "2") (pinfunction "2_2") (pintype "passive"))
      (node (ref "R19") (pin "2") (pinfunction "2_2") (pintype "passive"))
      (node (ref "T1") (pin "E") (pinfunction "E_E") (pintype "passive"))
    )
    (net (code "50") (name "Net-(IC3A-1Q)") (class "Default")
      (node (ref "IC3") (pin "19") (pinfunction "1Q_19") (pintype "tri_state"))
      (node (ref "IC5") (pin "27") (pinfunction "27_27") (pintype "passive"))
    )
    (net (code "51") (name "Net-(IC3A-2Q)") (class "Default")
      (node (ref "IC3") (pin "18") (pinfunction "2Q_18") (pintype "tri_state"))
      (node (ref "IC5") (pin "26") (pinfunction "26_26") (pintype "passive"))
    )
    (net (code "52") (name "Net-(IC3A-3Q)") (class "Default")
      (node (ref "IC3") (pin "17") (pinfunction "3Q_17") (pintype "tri_state"))
      (node (ref "IC5") (pin "23") (pinfunction "23_23") (pintype "passive"))
    )
    (net (code "53") (name "Net-(IC3A-4Q)") (class "Default")
      (node (ref "IC3") (pin "16") (pinfunction "4Q_16") (pintype "tri_state"))
      (node (ref "JS6") (pin "4") (pinfunction "4_4") (pintype "passive"))
    )
    (net (code "54") (name "Net-(IC3A-5Q)") (class "Default")
      (node (ref "IC3") (pin "15") (pinfunction "5Q_15") (pintype "tri_state"))
      (node (ref "IC5") (pin "4") (pinfunction "4_4") (pintype "passive"))
    )
    (net (code "55") (name "Net-(IC3A-6Q)") (class "Default")
      (node (ref "IC3") (pin "14") (pinfunction "6Q_14") (pintype "tri_state"))
      (node (ref "JS7") (pin "4") (pinfunction "4_4") (pintype "passive"))
    )
    (net (code "56") (name "Net-(IC3A-7Q)") (class "Default")
      (node (ref "IC3") (pin "13") (pinfunction "7Q_13") (pintype "tri_state"))
      (node (ref "JS4") (pin "6") (pinfunction "6_6") (pintype "passive"))
      (node (ref "JS8") (pin "4") (pinfunction "4_4") (pintype "passive"))
    )
    (net (code "57") (name "Net-(IC3A-8Q)") (class "Default")
      (node (ref "IC3") (pin "12") (pinfunction "8Q_12") (pintype "tri_state"))
      (node (ref "JS4") (pin "4") (pinfunction "4_4") (pintype "passive"))
    )
    (net (code "58") (name "Net-(IC4-CON)") (class "Default")
      (node (ref "C16") (pin "1") (pinfunction "1_1") (pintype "passive"))
      (node (ref "IC4") (pin "5") (pinfunction "CON_5") (pintype "input"))
    )
    (net (code "59") (name "Net-(IC4-OUT)") (class "Default")
      (node (ref "IC4") (pin "3") (pinfunction "OUT_3") (pintype "output"))
      (node (ref "Q1") (pin "2") (pinfunction "G_2") (pintype "passive"))
      (node (ref "Q2") (pin "2") (pinfunction "G_2") (pintype "passive"))
    )
    (net (code "60") (name "Net-(IC4-TRE)") (class "Default")
      (node (ref "C17") (pin "1") (pinfunction "1_1") (pintype "passive"))
      (node (ref "IC4") (pin "2") (pinfunction "TRI_2") (pintype "input"))
      (node (ref "IC4") (pin "6") (pinfunction "TRE_6") (pintype "input"))
      (node (ref "R34") (pin "2") (pinfunction "2_2") (pintype "passive"))
    )
    (net (code "61") (name "Net-(IC5-Pad1)") (class "Default")
      (node (ref "IC5") (pin "1") (pinfunction "1_1") (pintype "passive"))
      (node (ref "JS3") (pin "1") (pinfunction "1_1") (pintype "passive"))
      (node (ref "JS3") (pin "3") (pinfunction "3_3") (pintype "passive"))
      (node (ref "JS3") (pin "5") (pinfunction "5_5") (pintype "passive"))
    )
    (net (code "62") (name "Net-(IC5-Pad3)") (class "Default")
      (node (ref "IC5") (pin "3") (pinfunction "3_3") (pintype "passive"))
      (node (ref "JS4") (pin "1") (pinfunction "1_1") (pintype "passive"))
      (node (ref "JS4") (pin "3") (pinfunction "3_3") (pintype "passive"))
      (node (ref "JS4") (pin "5") (pinfunction "5_5") (pintype "passive"))
    )
    (net (code "63") (name "Net-(IC5-Pad13)") (class "Default")
      (node (ref "IC5") (pin "13") (pinfunction "13_13") (pintype "passive"))
      (node (ref "R1") (pin "2") (pinfunction "2_2") (pintype "passive"))
    )
    (net (code "64") (name "Net-(IC5-Pad14)") (class "Default")
      (node (ref "IC5") (pin "14") (pinfunction "14_14") (pintype "passive"))
      (node (ref "R2") (pin "2") (pinfunction "2_2") (pintype "passive"))
    )
    (net (code "65") (name "Net-(IC5-Pad15)") (class "Default")
      (node (ref "IC5") (pin "15") (pinfunction "15_15") (pintype "passive"))
      (node (ref "R3") (pin "2") (pinfunction "2_2") (pintype "passive"))
    )
    (net (code "66") (name "Net-(IC5-Pad17)") (class "Default")
      (node (ref "IC5") (pin "17") (pinfunction "17_17") (pintype "passive"))
      (node (ref "R4") (pin "2") (pinfunction "2_2") (pintype "passive"))
    )
    (net (code "67") (name "Net-(IC5-Pad18)") (class "Default")
      (node (ref "IC5") (pin "18") (pinfunction "18_18") (pintype "passive"))
      (node (ref "R5") (pin "2") (pinfunction "2_2") (pintype "passive"))
    )
    (net (code "68") (name "Net-(IC5-Pad19)") (class "Default")
      (node (ref "IC5") (pin "19") (pinfunction "19_19") (pintype "passive"))
      (node (ref "R6") (pin "2") (pinfunction "2_2") (pintype "passive"))
    )
    (net (code "69") (name "Net-(IC5-Pad20)") (class "Default")
      (node (ref "IC5") (pin "20") (pinfunction "20_20") (pintype "passive"))
      (node (ref "R7") (pin "2") (pinfunction "2_2") (pintype "passive"))
    )
    (net (code "70") (name "Net-(IC5-Pad21)") (class "Default")
      (node (ref "IC5") (pin "21") (pinfunction "21_21") (pintype "passive"))
      (node (ref "R8") (pin "2") (pinfunction "2_2") (pintype "passive"))
    )
    (net (code "71") (name "Net-(IC5-Pad24)") (class "Default")
      (node (ref "IC5") (pin "24") (pinfunction "24_24") (pintype "passive"))
      (node (ref "JS5") (pin "1") (pinfunction "1_1") (pintype "passive"))
      (node (ref "JS5") (pin "3") (pinfunction "3_3") (pintype "passive"))
    )
    (net (code "72") (name "Net-(IC5-Pad25)") (class "Default")
      (node (ref "IC5") (pin "25") (pinfunction "25_25") (pintype "passive"))
      (node (ref "JS6") (pin "1") (pinfunction "1_1") (pintype "passive"))
      (node (ref "JS6") (pin "3") (pinfunction "3_3") (pintype "passive"))
      (node (ref "JS6") (pin "5") (pinfunction "5_5") (pintype "passive"))
    )
    (net (code "73") (name "Net-(IC5-Pad28)") (class "Default")
      (node (ref "IC5") (pin "28") (pinfunction "28_28") (pintype "passive"))
      (node (ref "JS7") (pin "1") (pinfunction "1_1") (pintype "passive"))
      (node (ref "JS7") (pin "3") (pinfunction "3_3") (pintype "passive"))
    )
    (net (code "74") (name "Net-(IC5-Pad29)") (class "Default")
      (node (ref "IC5") (pin "29") (pinfunction "29_29") (pintype "passive"))
      (node (ref "JS8") (pin "1") (pinfunction "1_1") (pintype "passive"))
      (node (ref "JS8") (pin "3") (pinfunction "3_3") (pintype "passive"))
    )
    (net (code "75") (name "Net-(IC5-Pad30)") (class "Default")
      (node (ref "IC5") (pin "30") (pinfunction "30_30") (pintype "passive"))
      (node (ref "JS9") (pin "1") (pinfunction "1_1") (pintype "passive"))
      (node (ref "JS9") (pin "3") (pinfunction "3_3") (pintype "passive"))
      (node (ref "JS9") (pin "5") (pinfunction "5_5") (pintype "passive"))
    )
    (net (code "76") (name "Net-(IC5-Pad31)") (class "Default")
      (node (ref "IC5") (pin "31") (pinfunction "31_31") (pintype "passive"))
      (node (ref "JS10") (pin "1") (pinfunction "1_1") (pintype "passive"))
      (node (ref "JS10") (pin "3") (pinfunction "3_3") (pintype "passive"))
    )
    (net (code "77") (name "Net-(IC7-ADJ)") (class "Default")
      (node (ref "IC7") (pin "1") (pinfunction "ADJ_1") (pintype "input"))
      (node (ref "R23") (pin "1") (pinfunction "1_1") (pintype "passive"))
      (node (ref "R24") (pin "2") (pinfunction "S_2") (pintype "passive"))
      (node (ref "R24") (pin "3") (pinfunction "A_3") (pintype "passive"))
      (node (ref "R25") (pin "1") (pinfunction "E_1") (pintype "passive"))
      (node (ref "R25") (pin "2") (pinfunction "S_2") (pintype "passive"))
    )
    (net (code "78") (name "Net-(IC7-VO)") (class "Default")
      (node (ref "C15") (pin "+") (pinfunction "+_+") (pintype "passive"))
      (node (ref "IC7") (pin "2") (pinfunction "VO_2") (pintype "passive"))
      (node (ref "R23") (pin "2") (pinfunction "2_2") (pintype "passive"))
      (node (ref "R26") (pin "2") (pinfunction "2_2") (pintype "passive"))
      (node (ref "T5") (pin "1") (pinfunction "E_1") (pintype "passive"))
    )
    (net (code "79") (name "Net-(Q1-S)") (class "Default")
      (node (ref "C19") (pin "-") (pinfunction "-_-") (pintype "passive"))
      (node (ref "C9") (pin "-") (pinfunction "-_-") (pintype "passive"))
      (node (ref "Q1") (pin "3") (pinfunction "S_3") (pintype "passive"))
      (node (ref "Q2") (pin "3") (pinfunction "S_3") (pintype "passive"))
    )
    (net (code "80") (name "Net-(R12-A)") (class "Default")
      (node (ref "R12") (pin "2") (pinfunction "S_2") (pintype "passive"))
      (node (ref "R12") (pin "3") (pinfunction "A_3") (pintype "passive"))
      (node (ref "R13") (pin "2") (pinfunction "S_2") (pintype "passive"))
      (node (ref "R13") (pin "3") (pinfunction "A_3") (pintype "passive"))
      (node (ref "R14") (pin "2") (pinfunction "S_2") (pintype "passive"))
      (node (ref "R14") (pin "3") (pinfunction "A_3") (pintype "passive"))
      (node (ref "R15") (pin "2") (pinfunction "S_2") (pintype "passive"))
      (node (ref "R15") (pin "3") (pinfunction "A_3") (pintype "passive"))
      (node (ref "R16") (pin "2") (pinfunction "S_2") (pintype "passive"))
      (node (ref "R16") (pin "3") (pinfunction "A_3") (pintype "passive"))
      (node (ref "R17") (pin "2") (pinfunction "S_2") (pintype "passive"))
      (node (ref "R17") (pin "3") (pinfunction "A_3") (pintype "passive"))
      (node (ref "R18") (pin "1") (pinfunction "1_1") (pintype "passive"))
      (node (ref "R31") (pin "1") (pinfunction "1_1") (pintype "passive"))
      (node (ref "R33") (pin "2") (pinfunction "S_2") (pintype "passive"))
      (node (ref "R33") (pin "3") (pinfunction "A_3") (pintype "passive"))
    )
    (net (code "81") (name "Net-(R12-E)") (class "Default")
      (node (ref "JS2") (pin "2") (pinfunction "2_2") (pintype "passive"))
      (node (ref "R12") (pin "1") (pinfunction "E_1") (pintype "passive"))
    )
    (net (code "82") (name "Net-(R13-E)") (class "Default")
      (node (ref "JS2") (pin "4") (pinfunction "4_4") (pintype "passive"))
      (node (ref "R13") (pin "1") (pinfunction "E_1") (pintype "passive"))
    )
    (net (code "83") (name "Net-(R14-E)") (class "Default")
      (node (ref "JS2") (pin "6") (pinfunction "6_6") (pintype "passive"))
      (node (ref "R14") (pin "1") (pinfunction "E_1") (pintype "passive"))
    )
    (net (code "84") (name "Net-(R15-E)") (class "Default")
      (node (ref "JS2") (pin "8") (pinfunction "8_8") (pintype "passive"))
      (node (ref "R15") (pin "1") (pinfunction "E_1") (pintype "passive"))
    )
    (net (code "85") (name "Net-(R16-E)") (class "Default")
      (node (ref "JS2") (pin "10") (pinfunction "10_10") (pintype "passive"))
      (node (ref "R16") (pin "1") (pinfunction "E_1") (pintype "passive"))
    )
    (net (code "86") (name "Net-(R19-Pad1)") (class "Default")
      (node (ref "R19") (pin "1") (pinfunction "1_1") (pintype "passive"))
      (node (ref "R20") (pin "2") (pinfunction "2_2") (pintype "passive"))
      (node (ref "T1") (pin "B") (pinfunction "B_B") (pintype "passive"))
    )
    (net (code "87") (name "Net-(R20-Pad1)") (class "Default")
      (node (ref "R20") (pin "1") (pinfunction "1_1") (pintype "passive"))
      (node (ref "T2") (pin "C") (pinfunction "C_C") (pintype "passive"))
    )
    (net (code "88") (name "Net-(R21-Pad2)") (class "Default")
      (node (ref "R21") (pin "2") (pinfunction "2_2") (pintype "passive"))
      (node (ref "T2") (pin "B") (pinfunction "B_B") (pintype "passive"))
    )
    (net (code "89") (name "Net-(R24-E)") (class "Default")
      (node (ref "R24") (pin "1") (pinfunction "E_1") (pintype "passive"))
      (node (ref "T3") (pin "3") (pinfunction "C_3") (pintype "passive"))
    )
    (net (code "90") (name "Net-(R33-E)") (class "Default")
      (node (ref "JS2") (pin "12") (pinfunction "12_12") (pintype "passive"))
      (node (ref "R33") (pin "1") (pinfunction "E_1") (pintype "passive"))
    )
    (net (code "91") (name "Net-(RT-C)") (class "Default")
      (node (ref "R10") (pin "1") (pinfunction "1_1") (pintype "passive"))
      (node (ref "RT") (pin "K") (pinfunction "C_K") (pintype "passive"))
    )
    (net (code "92") (name "Net-(T3-B)") (class "Default")
      (node (ref "R30") (pin "2") (pinfunction "2_2") (pintype "passive"))
      (node (ref "T3") (pin "2") (pinfunction "B_2") (pintype "passive"))
    )
    (net (code "93") (name "Net-(T4-B)") (class "Default")
      (node (ref "R29") (pin "2") (pinfunction "2_2") (pintype "passive"))
      (node (ref "T4") (pin "2") (pinfunction "B_2") (pintype "passive"))
    )
    (net (code "94") (name "Net-(T4-C)") (class "Default")
      (node (ref "R27") (pin "1") (pinfunction "1_1") (pintype "passive"))
      (node (ref "T4") (pin "3") (pinfunction "C_3") (pintype "passive"))
    )
    (net (code "95") (name "Net-(T5-B)") (class "Default")
      (node (ref "R26") (pin "1") (pinfunction "1_1") (pintype "passive"))
      (node (ref "R27") (pin "2") (pinfunction "2_2") (pintype "passive"))
      (node (ref "T5") (pin "2") (pinfunction "B_2") (pintype "passive"))
    )
    (net (code "96") (name "Net-(T5-C)") (class "Default")
      (node (ref "IC5") (pin "32") (pinfunction "32_32") (pintype "passive"))
      (node (ref "JS1") (pin "2") (pinfunction "2_2") (pintype "passive"))
      (node (ref "JS7") (pin "2") (pinfunction "2_2") (pintype "passive"))
      (node (ref "JS9") (pin "2") (pinfunction "2_2") (pintype "passive"))
      (node (ref "R28") (pin "2") (pinfunction "2_2") (pintype "passive"))
      (node (ref "T5") (pin "3") (pinfunction "C_3") (pintype "passive"))
      (node (ref "UXX") (pin "MP") (pinfunction "MP_MP") (pintype "passive"))
    )
    (net (code "97") (name "Net-(U$6-D+)") (class "Default")
      (node (ref "CN1") (pin "D+") (pinfunction "D+_D+") (pintype "bidirectional"))
      (node (ref "R32") (pin "2") (pinfunction "2_2") (pintype "passive"))
      (node (ref "U$6") (pin "5") (pinfunction "D+_5") (pintype "bidirectional"))
    )
    (net (code "98") (name "Net-(U$6-D-)") (class "Default")
      (node (ref "CN1") (pin "D-") (pinfunction "D-_D-") (pintype "bidirectional"))
      (node (ref "U$6") (pin "6") (pinfunction "D-_6") (pintype "bidirectional"))
    )
    (net (code "99") (name "Net-(U$6-V3)") (class "Default")
      (node (ref "C3") (pin "1") (pinfunction "1_1") (pintype "passive"))
      (node (ref "U$6") (pin "4") (pinfunction "V3_4") (pintype "bidirectional"))
    )
    (net (code "100") (name "Net-(U$6-XI)") (class "Default")
      (node (ref "C1") (pin "1") (pinfunction "1_1") (pintype "passive"))
      (node (ref "U$6") (pin "7") (pinfunction "XI_7") (pintype "bidirectional"))
      (node (ref "Y1") (pin "1") (pinfunction "1_1") (pintype "passive"))
    )
    (net (code "101") (name "Net-(U$6-XO)") (class "Default")
      (node (ref "C2") (pin "1") (pinfunction "1_1") (pintype "passive"))
      (node (ref "U$6") (pin "8") (pinfunction "XO_8") (pintype "bidirectional"))
      (node (ref "Y1") (pin "2") (pinfunction "2_2") (pintype "passive"))
    )
    (net (code "102") (name "unconnected-(CN1-PadID)") (class "Default")
      (node (ref "CN1") (pin "ID") (pinfunction "ID_ID") (pintype "bidirectional"))
    )
    (net (code "103") (name "unconnected-(IC1-ALE-Pad30)") (class "Default")
      (node (ref "IC1") (pin "30") (pinfunction "ALE_30") (pintype "bidirectional"))
    )
    (net (code "104") (name "unconnected-(JS1-Pad4)") (class "Default")
      (node (ref "JS1") (pin "4") (pinfunction "4_4") (pintype "passive"))
    )
    (net (code "105") (name "unconnected-(JS3-Pad7)") (class "Default")
      (node (ref "JS3") (pin "7") (pinfunction "7_7") (pintype "passive"))
    )
    (net (code "106") (name "unconnected-(JS3-Pad8)") (class "Default")
      (node (ref "JS3") (pin "8") (pinfunction "8_8") (pintype "passive"))
    )
    (net (code "107") (name "unconnected-(JS4-Pad7)") (class "Default")
      (node (ref "JS4") (pin "7") (pinfunction "7_7") (pintype "passive"))
    )
    (net (code "108") (name "unconnected-(JS4-Pad8)") (class "Default")
      (node (ref "JS4") (pin "8") (pinfunction "8_8") (pintype "passive"))
    )
    (net (code "109") (name "unconnected-(JS5-Pad5)") (class "Default")
      (node (ref "JS5") (pin "5") (pinfunction "5_5") (pintype "passive"))
    )
    (net (code "110") (name "unconnected-(JS5-Pad6)") (class "Default")
      (node (ref "JS5") (pin "6") (pinfunction "6_6") (pintype "passive"))
    )
    (net (code "111") (name "unconnected-(JS5-Pad7)") (class "Default")
      (node (ref "JS5") (pin "7") (pinfunction "7_7") (pintype "passive"))
    )
    (net (code "112") (name "unconnected-(JS5-Pad8)") (class "Default")
      (node (ref "JS5") (pin "8") (pinfunction "8_8") (pintype "passive"))
    )
    (net (code "113") (name "unconnected-(JS6-Pad7)") (class "Default")
      (node (ref "JS6") (pin "7") (pinfunction "7_7") (pintype "passive"))
    )
    (net (code "114") (name "unconnected-(JS6-Pad8)") (class "Default")
      (node (ref "JS6") (pin "8") (pinfunction "8_8") (pintype "passive"))
    )
    (net (code "115") (name "unconnected-(JS7-Pad5)") (class "Default")
      (node (ref "JS7") (pin "5") (pinfunction "5_5") (pintype "passive"))
    )
    (net (code "116") (name "unconnected-(JS7-Pad6)") (class "Default")
      (node (ref "JS7") (pin "6") (pinfunction "6_6") (pintype "passive"))
    )
    (net (code "117") (name "unconnected-(JS7-Pad7)") (class "Default")
      (node (ref "JS7") (pin "7") (pinfunction "7_7") (pintype "passive"))
    )
    (net (code "118") (name "unconnected-(JS7-Pad8)") (class "Default")
      (node (ref "JS7") (pin "8") (pinfunction "8_8") (pintype "passive"))
    )
    (net (code "119") (name "unconnected-(JS8-Pad5)") (class "Default")
      (node (ref "JS8") (pin "5") (pinfunction "5_5") (pintype "passive"))
    )
    (net (code "120") (name "unconnected-(JS8-Pad6)") (class "Default")
      (node (ref "JS8") (pin "6") (pinfunction "6_6") (pintype "passive"))
    )
    (net (code "121") (name "unconnected-(JS8-Pad7)") (class "Default")
      (node (ref "JS8") (pin "7") (pinfunction "7_7") (pintype "passive"))
    )
    (net (code "122") (name "unconnected-(JS8-Pad8)") (class "Default")
      (node (ref "JS8") (pin "8") (pinfunction "8_8") (pintype "passive"))
    )
    (net (code "123") (name "unconnected-(JS9-Pad7)") (class "Default")
      (node (ref "JS9") (pin "7") (pinfunction "7_7") (pintype "passive"))
    )
    (net (code "124") (name "unconnected-(JS9-Pad8)") (class "Default")
      (node (ref "JS9") (pin "8") (pinfunction "8_8") (pintype "passive"))
    )
    (net (code "125") (name "unconnected-(JS10-Pad5)") (class "Default")
      (node (ref "JS10") (pin "5") (pinfunction "5_5") (pintype "passive"))
    )
    (net (code "126") (name "unconnected-(JS10-Pad6)") (class "Default")
      (node (ref "JS10") (pin "6") (pinfunction "6_6") (pintype "passive"))
    )
    (net (code "127") (name "unconnected-(JS10-Pad7)") (class "Default")
      (node (ref "JS10") (pin "7") (pinfunction "7_7") (pintype "passive"))
    )
    (net (code "128") (name "unconnected-(JS10-Pad8)") (class "Default")
      (node (ref "JS10") (pin "8") (pinfunction "8_8") (pintype "passive"))
    )
    (net (code "129") (name "unconnected-(U$6-DCD#-Pad12)") (class "Default")
      (node (ref "U$6") (pin "12") (pinfunction "DCD#_12") (pintype "bidirectional"))
    )
    (net (code "130") (name "unconnected-(U$6-DSR#-Pad10)") (class "Default")
      (node (ref "U$6") (pin "10") (pinfunction "DSR#_10") (pintype "bidirectional"))
    )
    (net (code "131") (name "unconnected-(U$6-DTR#-Pad13)") (class "Default")
      (node (ref "U$6") (pin "13") (pinfunction "DTR#_13") (pintype "bidirectional"))
    )
    (net (code "132") (name "unconnected-(U$6-R232-Pad15)") (class "Default")
      (node (ref "U$6") (pin "15") (pinfunction "R232_15") (pintype "bidirectional"))
    )
    (net (code "133") (name "unconnected-(U$6-RI#-Pad11)") (class "Default")
      (node (ref "U$6") (pin "11") (pinfunction "RI#_11") (pintype "bidirectional"))
    )
  )
)
